# ITAC.net
KiCad netlist of a schematic drawn in Altium Designer
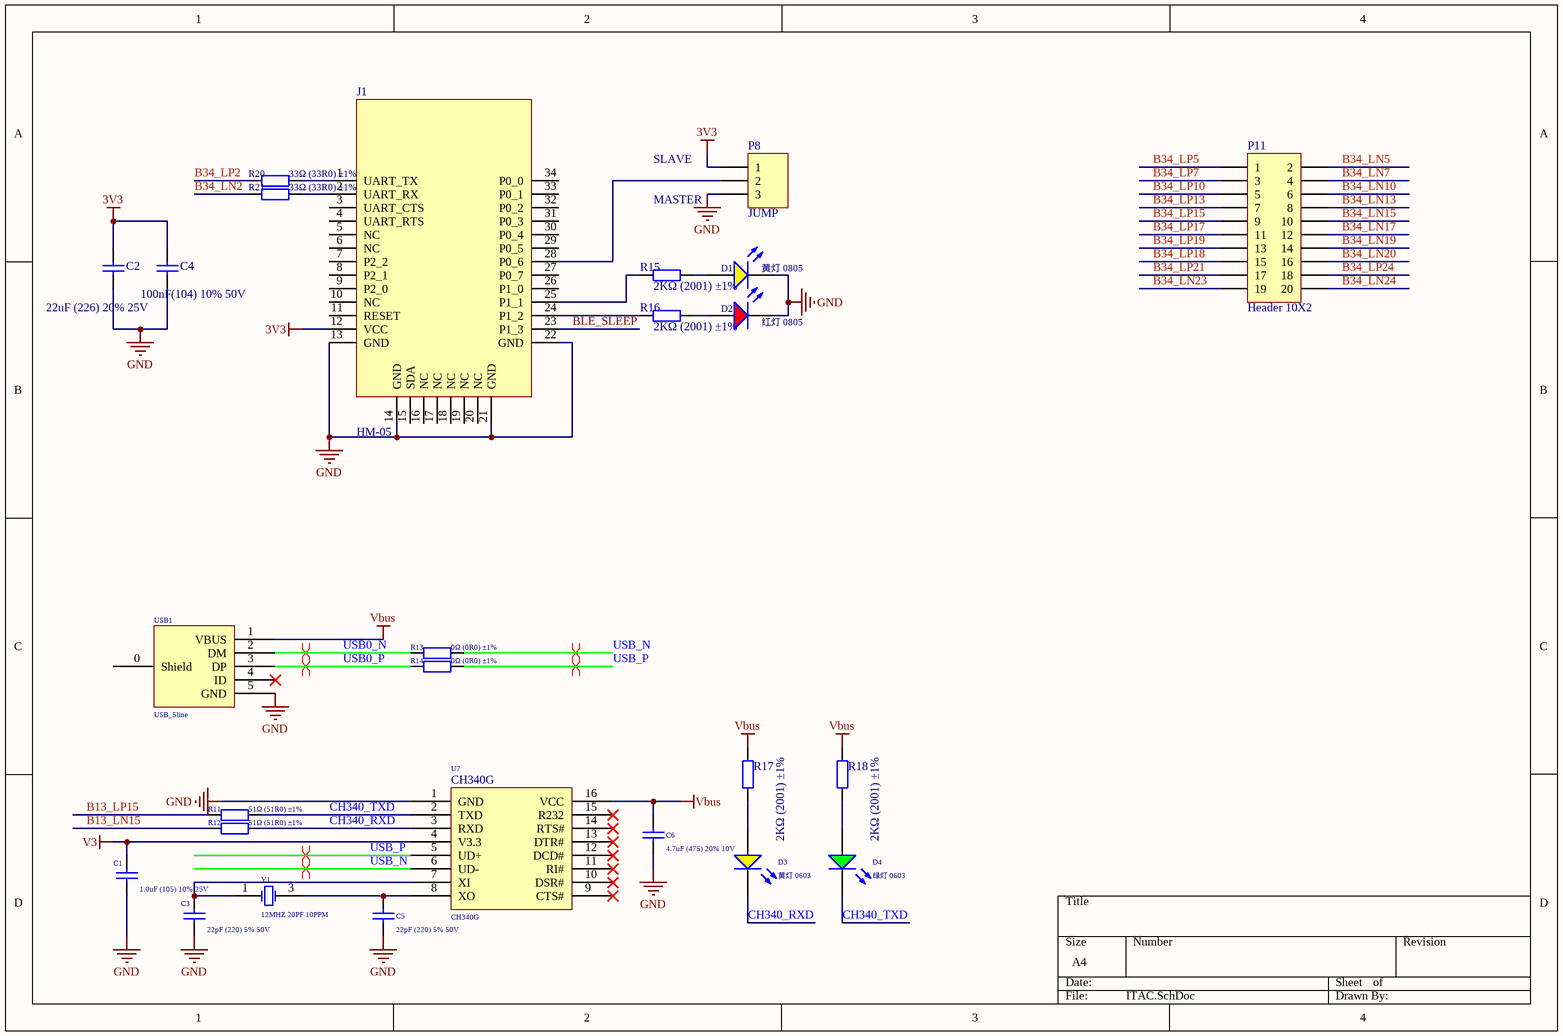
[diagram p0: ITAC.SchDoc]

(export (version "E")
  (design (tool "Eeschema 10.0.6"))
  (components
    (comp (ref "C1")
      (value "1.0uF (105) 10% 25V")
      (footprint "0402_C")
      (description "贴片电容")
      (libsource (lib "Miscellaneous Devices LC") (part "0402 1.0uF (105) 10% 25V"))
    )
    (comp (ref "C2")
      (value "22uF (226) 20% 25V")
      (footprint "0805_C")
      (description "贴片电容")
      (libsource (lib "Miscellaneous Devices LC") (part "0805 22uF (226) 20% 25V"))
    )
    (comp (ref "C3")
      (value "22pF (220) 5% 50V")
      (footprint "0402_C")
      (description "贴片电容")
      (libsource (lib "Miscellaneous Devices LC") (part "0402 22pF (220) 5% 50V"))
    )
    (comp (ref "C4")
      (value "100nF(104) 10% 50V")
      (footprint "0805_C")
      (description "贴片电容")
      (libsource (lib "Miscellaneous Devices LC") (part "0805 100nF(104) 10% 50V"))
    )
    (comp (ref "C5")
      (value "22pF (220) 5% 50V")
      (footprint "0402_C")
      (description "贴片电容")
      (libsource (lib "Miscellaneous Devices LC") (part "0402 22pF (220) 5% 50V"))
    )
    (comp (ref "C6")
      (value "4.7uF (475) 20% 10V")
      (footprint "0402_C")
      (description "贴片电容")
      (libsource (lib "Miscellaneous Devices LC") (part "0402 4.7uF (475) 20% 10V"))
    )
    (comp (ref "D1")
      (value "黄灯 0805")
      (footprint "0805_LED_S1")
      (description "发光二极管")
      (libsource (lib "Miscellaneous Devices LC") (part "0805 黄灯"))
    )
    (comp (ref "D2")
      (value "红灯 0805")
      (footprint "0805_LED_S1")
      (description "发光二极管")
      (libsource (lib "Miscellaneous Devices LC") (part "0805 红灯"))
    )
    (comp (ref "D3")
      (value "黄灯 0603")
      (footprint "0603_LED_S1")
      (description "发光二极管")
      (libsource (lib "Miscellaneous Devices LC") (part "0603 黄灯"))
    )
    (comp (ref "D4")
      (value "绿灯 0603")
      (footprint "0603_LED_S1")
      (description "发光二极管")
      (libsource (lib "Miscellaneous Devices LC") (part "0603 绿灯"))
    )
    (comp (ref "J1") (value "HM-05") (footprint "BT05") (libsource (lib "zynqEXP_Schlib") (part "HM-05")))
    (comp (ref "P8")
      (value "JUMP")
      (footprint "HDR1X3")
      (description "Header, 3-Pin")
      (fields (field (name "PUBLISHER") "Altium Limited"))
      (libsource (lib "Miscellaneous Connectors") (part "Header 3"))
    )
    (comp (ref "P11")
      (value "Header 10X2")
      (footprint "HDR2X10")
      (description "Header, 10-Pin, Dual row")
      (fields (field (name "PUBLISHER") "Altium Limited"))
      (libsource (lib "Sparks") (part "Header 10X2"))
    )
    (comp (ref "R11")
      (value "51Ω (51R0) ±1%")
      (footprint "0402_R")
      (description "贴片电阻")
      (libsource (lib "Miscellaneous Devices LC") (part "0402 51Ω (51R0) 1%"))
    )
    (comp (ref "R12")
      (value "51Ω (51R0) ±1%")
      (footprint "0402_R")
      (description "贴片电阻")
      (libsource (lib "Miscellaneous Devices LC") (part "0402 51Ω (51R0) 1%"))
    )
    (comp (ref "R13")
      (value "0Ω (0R0) ±1%")
      (footprint "0402_R")
      (description "贴片电阻")
      (libsource (lib "Miscellaneous Devices LC") (part "0402 0Ω (0R0) 1%"))
    )
    (comp (ref "R14")
      (value "0Ω (0R0) ±1%")
      (footprint "0402_R")
      (description "贴片电阻")
      (libsource (lib "Miscellaneous Devices LC") (part "0402 0Ω (0R0) 1%"))
    )
    (comp (ref "R15")
      (value "2KΩ (2001) ±1%")
      (footprint "0805_R")
      (description "贴片电阻")
      (libsource (lib "Miscellaneous Devices LC") (part "0805 2KΩ (2001) 1%"))
    )
    (comp (ref "R16")
      (value "2KΩ (2001) ±1%")
      (footprint "0805_R")
      (description "贴片电阻")
      (libsource (lib "Miscellaneous Devices LC") (part "0805 2KΩ (2001) 1%"))
    )
    (comp (ref "R17")
      (value "2KΩ (2001) ±1%")
      (footprint "0402_R")
      (description "贴片电阻")
      (libsource (lib "") (part "0402 2KΩ (2001) 1%_1"))
    )
    (comp (ref "R18")
      (value "2KΩ (2001) ±1%")
      (footprint "0402_R")
      (description "贴片电阻")
      (libsource (lib "Miscellaneous Devices LC") (part "0402 2KΩ (2001) 1%"))
    )
    (comp (ref "R20")
      (value "33Ω (33R0) ±1%")
      (footprint "0402_R")
      (description "贴片电阻")
      (libsource (lib "Miscellaneous Devices LC") (part "0402 33Ω (33R0) 1%"))
    )
    (comp (ref "R21")
      (value "33Ω (33R0) ±1%")
      (footprint "0402_R")
      (description "贴片电阻")
      (libsource (lib "Miscellaneous Devices LC") (part "0402 33Ω (33R0) 1%"))
    )
    (comp (ref "U7")
      (value "CH340G")
      (footprint "SOIC-16_150mil")
      (description "USB")
      (libsource (lib "Miscellaneous Devices LC") (part "CH340G_[C14267]"))
    )
    (comp (ref "USB1")
      (value "USB_5line")
      (footprint "USB-MICRO-5P-2F")
      (libsource (lib "2号库") (part "USB_5line"))
    )
    (comp (ref "Y1")
      (value "12MHZ 20PF 10PPM")
      (footprint "SMD-3225_4P")
      (description "贴片晶振")
      (libsource (lib "Miscellaneous Devices LC") (part "SMD-3225_4P  12MHZ 20PF 10PPM"))
    )
  )
  (nets
    (net (code "1") (name "/B13_LN15") (class "Default")
      (node (ref "R12") (pin "1") (pinfunction "1_1") (pintype "passive"))
    )
    (net (code "2") (name "/B13_LP15") (class "Default")
      (node (ref "R11") (pin "1") (pinfunction "1_1") (pintype "passive"))
    )
    (net (code "3") (name "/B34_LN2") (class "Default")
      (node (ref "R21") (pin "1") (pinfunction "1_1") (pintype "passive"))
    )
    (net (code "4") (name "/B34_LN5") (class "Default")
      (node (ref "P11") (pin "2") (pinfunction "2_2") (pintype "passive"))
    )
    (net (code "5") (name "/B34_LN7") (class "Default")
      (node (ref "P11") (pin "4") (pinfunction "4_4") (pintype "passive"))
    )
    (net (code "6") (name "/B34_LN10") (class "Default")
      (node (ref "P11") (pin "6") (pinfunction "6_6") (pintype "passive"))
    )
    (net (code "7") (name "/B34_LN13") (class "Default")
      (node (ref "P11") (pin "8") (pinfunction "8_8") (pintype "passive"))
    )
    (net (code "8") (name "/B34_LN15") (class "Default")
      (node (ref "P11") (pin "10") (pinfunction "10_10") (pintype "passive"))
    )
    (net (code "9") (name "/B34_LN17") (class "Default")
      (node (ref "P11") (pin "12") (pinfunction "12_12") (pintype "passive"))
    )
    (net (code "10") (name "/B34_LN19") (class "Default")
      (node (ref "P11") (pin "14") (pinfunction "14_14") (pintype "passive"))
    )
    (net (code "11") (name "/B34_LN20") (class "Default")
      (node (ref "P11") (pin "16") (pinfunction "16_16") (pintype "passive"))
    )
    (net (code "12") (name "/B34_LN23") (class "Default")
      (node (ref "P11") (pin "19") (pinfunction "19_19") (pintype "passive"))
    )
    (net (code "13") (name "/B34_LN24") (class "Default")
      (node (ref "P11") (pin "20") (pinfunction "20_20") (pintype "passive"))
    )
    (net (code "14") (name "/B34_LP2") (class "Default")
      (node (ref "R20") (pin "1") (pinfunction "1_1") (pintype "passive"))
    )
    (net (code "15") (name "/B34_LP5") (class "Default")
      (node (ref "P11") (pin "1") (pinfunction "1_1") (pintype "passive"))
    )
    (net (code "16") (name "/B34_LP7") (class "Default")
      (node (ref "P11") (pin "3") (pinfunction "3_3") (pintype "passive"))
    )
    (net (code "17") (name "/B34_LP10") (class "Default")
      (node (ref "P11") (pin "5") (pinfunction "5_5") (pintype "passive"))
    )
    (net (code "18") (name "/B34_LP13") (class "Default")
      (node (ref "P11") (pin "7") (pinfunction "7_7") (pintype "passive"))
    )
    (net (code "19") (name "/B34_LP15") (class "Default")
      (node (ref "P11") (pin "9") (pinfunction "9_9") (pintype "passive"))
    )
    (net (code "20") (name "/B34_LP17") (class "Default")
      (node (ref "P11") (pin "11") (pinfunction "11_11") (pintype "passive"))
    )
    (net (code "21") (name "/B34_LP18") (class "Default")
      (node (ref "P11") (pin "15") (pinfunction "15_15") (pintype "passive"))
    )
    (net (code "22") (name "/B34_LP19") (class "Default")
      (node (ref "P11") (pin "13") (pinfunction "13_13") (pintype "passive"))
    )
    (net (code "23") (name "/B34_LP21") (class "Default")
      (node (ref "P11") (pin "17") (pinfunction "17_17") (pintype "passive"))
    )
    (net (code "24") (name "/B34_LP24") (class "Default")
      (node (ref "P11") (pin "18") (pinfunction "18_18") (pintype "passive"))
    )
    (net (code "25") (name "/BLE_SLEEP") (class "Default")
      (node (ref "J1") (pin "23") (pinfunction "P1_3_23") (pintype "passive"))
    )
    (net (code "26") (name "/CH340_RXD") (class "Default")
      (node (ref "D3") (pin "K") (pinfunction "K_K") (pintype "passive"))
      (node (ref "R12") (pin "2") (pinfunction "2_2") (pintype "passive"))
      (node (ref "U7") (pin "3") (pinfunction "RXD_3") (pintype "passive"))
    )
    (net (code "27") (name "/CH340_TXD") (class "Default")
      (node (ref "D4") (pin "K") (pinfunction "K_K") (pintype "passive"))
      (node (ref "R11") (pin "2") (pinfunction "2_2") (pintype "passive"))
      (node (ref "U7") (pin "2") (pinfunction "TXD_2") (pintype "passive"))
    )
    (net (code "28") (name "/USB0_N") (class "Default")
      (node (ref "R13") (pin "1") (pinfunction "1_1") (pintype "passive"))
      (node (ref "USB1") (pin "2") (pinfunction "DM_2") (pintype "passive"))
    )
    (net (code "29") (name "/USB0_P") (class "Default")
      (node (ref "R14") (pin "1") (pinfunction "1_1") (pintype "passive"))
      (node (ref "USB1") (pin "3") (pinfunction "DP_3") (pintype "passive"))
    )
    (net (code "30") (name "/USB_N") (class "Default")
      (node (ref "R13") (pin "2") (pinfunction "2_2") (pintype "passive"))
      (node (ref "U7") (pin "6") (pinfunction "UD-_6") (pintype "passive"))
    )
    (net (code "31") (name "/USB_P") (class "Default")
      (node (ref "R14") (pin "2") (pinfunction "2_2") (pintype "passive"))
      (node (ref "U7") (pin "5") (pinfunction "UD+_5") (pintype "passive"))
    )
    (net (code "32") (name "3V3") (class "Default")
      (node (ref "C2") (pin "2") (pinfunction "2_2") (pintype "passive"))
      (node (ref "C4") (pin "2") (pinfunction "2_2") (pintype "passive"))
      (node (ref "J1") (pin "12") (pinfunction "VCC_12") (pintype "passive"))
      (node (ref "P8") (pin "1") (pinfunction "1_1") (pintype "passive"))
    )
    (net (code "33") (name "GND") (class "Default")
      (node (ref "C1") (pin "1") (pinfunction "1_1") (pintype "passive"))
      (node (ref "C2") (pin "1") (pinfunction "1_1") (pintype "passive"))
      (node (ref "C3") (pin "1") (pinfunction "1_1") (pintype "passive"))
      (node (ref "C4") (pin "1") (pinfunction "1_1") (pintype "passive"))
      (node (ref "C5") (pin "1") (pinfunction "1_1") (pintype "passive"))
      (node (ref "C6") (pin "1") (pinfunction "1_1") (pintype "passive"))
      (node (ref "D1") (pin "K") (pinfunction "K_K") (pintype "passive"))
      (node (ref "D2") (pin "K") (pinfunction "K_K") (pintype "passive"))
      (node (ref "J1") (pin "13") (pinfunction "GND_13") (pintype "passive"))
      (node (ref "J1") (pin "14") (pinfunction "GND_14") (pintype "passive"))
      (node (ref "J1") (pin "21") (pinfunction "GND_21") (pintype "passive"))
      (node (ref "J1") (pin "22") (pinfunction "GND_22") (pintype "passive"))
      (node (ref "P8") (pin "3") (pinfunction "3_3") (pintype "passive"))
      (node (ref "U7") (pin "1") (pinfunction "GND_1") (pintype "passive"))
      (node (ref "USB1") (pin "5") (pinfunction "GND_5") (pintype "passive"))
    )
    (net (code "34") (name "Net-(D1-PadA)") (class "Default")
      (node (ref "D1") (pin "A") (pinfunction "A_A") (pintype "passive"))
      (node (ref "R15") (pin "2") (pinfunction "2_2") (pintype "passive"))
    )
    (net (code "35") (name "Net-(D2-PadA)") (class "Default")
      (node (ref "D2") (pin "A") (pinfunction "A_A") (pintype "passive"))
      (node (ref "R16") (pin "2") (pinfunction "2_2") (pintype "passive"))
    )
    (net (code "36") (name "Net-(D3-PadA)") (class "Default")
      (node (ref "D3") (pin "A") (pinfunction "A_A") (pintype "passive"))
      (node (ref "R17") (pin "1") (pinfunction "1_1") (pintype "passive"))
    )
    (net (code "37") (name "Net-(D4-PadA)") (class "Default")
      (node (ref "D4") (pin "A") (pinfunction "A_A") (pintype "passive"))
      (node (ref "R18") (pin "2") (pinfunction "2_2") (pintype "passive"))
    )
    (net (code "38") (name "Net-(J1-P0_6)") (class "Default")
      (node (ref "J1") (pin "28") (pinfunction "P0_6_28") (pintype "passive"))
      (node (ref "P8") (pin "2") (pinfunction "2_2") (pintype "passive"))
    )
    (net (code "39") (name "Net-(J1-P1_1)") (class "Default")
      (node (ref "J1") (pin "25") (pinfunction "P1_1_25") (pintype "passive"))
      (node (ref "R15") (pin "1") (pinfunction "1_1") (pintype "passive"))
    )
    (net (code "40") (name "Net-(J1-P1_2)") (class "Default")
      (node (ref "J1") (pin "24") (pinfunction "P1_2_24") (pintype "passive"))
      (node (ref "R16") (pin "1") (pinfunction "1_1") (pintype "passive"))
    )
    (net (code "41") (name "Net-(J1-UART_RX)") (class "Default")
      (node (ref "J1") (pin "2") (pinfunction "UART_RX_2") (pintype "passive"))
      (node (ref "R21") (pin "2") (pinfunction "2_2") (pintype "passive"))
    )
    (net (code "42") (name "Net-(J1-UART_TX)") (class "Default")
      (node (ref "J1") (pin "1") (pinfunction "UART_TX_1") (pintype "passive"))
      (node (ref "R20") (pin "2") (pinfunction "2_2") (pintype "passive"))
    )
    (net (code "43") (name "Net-(U7-XI)") (class "Default")
      (node (ref "C3") (pin "2") (pinfunction "2_2") (pintype "passive"))
      (node (ref "U7") (pin "7") (pinfunction "XI_7") (pintype "passive"))
      (node (ref "Y1") (pin "1") (pinfunction "OSC1_1") (pintype "passive"))
    )
    (net (code "44") (name "Net-(U7-XO)") (class "Default")
      (node (ref "C5") (pin "2") (pinfunction "2_2") (pintype "passive"))
      (node (ref "U7") (pin "8") (pinfunction "XO_8") (pintype "passive"))
      (node (ref "Y1") (pin "3") (pinfunction "OSC2_3") (pintype "passive"))
    )
    (net (code "45") (name "V3") (class "Default")
      (node (ref "C1") (pin "2") (pinfunction "2_2") (pintype "passive"))
      (node (ref "U7") (pin "4") (pinfunction "V3.3_4") (pintype "passive"))
    )
    (net (code "46") (name "Vbus") (class "Default")
      (node (ref "C6") (pin "2") (pinfunction "2_2") (pintype "passive"))
      (node (ref "R17") (pin "2") (pinfunction "2_2") (pintype "passive"))
      (node (ref "R18") (pin "1") (pinfunction "1_1") (pintype "passive"))
      (node (ref "U7") (pin "16") (pinfunction "VCC_16") (pintype "passive"))
      (node (ref "USB1") (pin "1") (pinfunction "VBUS_1") (pintype "passive"))
    )
    (net (code "47") (name "unconnected-(J1-NC-Pad5)") (class "Default")
      (node (ref "J1") (pin "5") (pinfunction "NC_5") (pintype "passive"))
    )
    (net (code "48") (name "unconnected-(J1-NC-Pad6)") (class "Default")
      (node (ref "J1") (pin "6") (pinfunction "NC_6") (pintype "passive"))
    )
    (net (code "49") (name "unconnected-(J1-NC-Pad10)") (class "Default")
      (node (ref "J1") (pin "10") (pinfunction "NC_10") (pintype "passive"))
    )
    (net (code "50") (name "unconnected-(J1-NC-Pad16)") (class "Default")
      (node (ref "J1") (pin "16") (pinfunction "NC_16") (pintype "passive"))
    )
    (net (code "51") (name "unconnected-(J1-NC-Pad17)") (class "Default")
      (node (ref "J1") (pin "17") (pinfunction "NC_17") (pintype "passive"))
    )
    (net (code "52") (name "unconnected-(J1-NC-Pad18)") (class "Default")
      (node (ref "J1") (pin "18") (pinfunction "NC_18") (pintype "passive"))
    )
    (net (code "53") (name "unconnected-(J1-NC-Pad19)") (class "Default")
      (node (ref "J1") (pin "19") (pinfunction "NC_19") (pintype "passive"))
    )
    (net (code "54") (name "unconnected-(J1-NC-Pad20)") (class "Default")
      (node (ref "J1") (pin "20") (pinfunction "NC_20") (pintype "passive"))
    )
    (net (code "55") (name "unconnected-(J1-P0_0-Pad34)") (class "Default")
      (node (ref "J1") (pin "34") (pinfunction "P0_0_34") (pintype "passive"))
    )
    (net (code "56") (name "unconnected-(J1-P0_1-Pad33)") (class "Default")
      (node (ref "J1") (pin "33") (pinfunction "P0_1_33") (pintype "passive"))
    )
    (net (code "57") (name "unconnected-(J1-P0_2-Pad32)") (class "Default")
      (node (ref "J1") (pin "32") (pinfunction "P0_2_32") (pintype "passive"))
    )
    (net (code "58") (name "unconnected-(J1-P0_3-Pad31)") (class "Default")
      (node (ref "J1") (pin "31") (pinfunction "P0_3_31") (pintype "passive"))
    )
    (net (code "59") (name "unconnected-(J1-P0_4-Pad30)") (class "Default")
      (node (ref "J1") (pin "30") (pinfunction "P0_4_30") (pintype "passive"))
    )
    (net (code "60") (name "unconnected-(J1-P0_5-Pad29)") (class "Default")
      (node (ref "J1") (pin "29") (pinfunction "P0_5_29") (pintype "passive"))
    )
    (net (code "61") (name "unconnected-(J1-P0_7-Pad27)") (class "Default")
      (node (ref "J1") (pin "27") (pinfunction "P0_7_27") (pintype "passive"))
    )
    (net (code "62") (name "unconnected-(J1-P1_0-Pad26)") (class "Default")
      (node (ref "J1") (pin "26") (pinfunction "P1_0_26") (pintype "passive"))
    )
    (net (code "63") (name "unconnected-(J1-P2_0-Pad9)") (class "Default")
      (node (ref "J1") (pin "9") (pinfunction "P2_0_9") (pintype "passive"))
    )
    (net (code "64") (name "unconnected-(J1-P2_1-Pad8)") (class "Default")
      (node (ref "J1") (pin "8") (pinfunction "P2_1_8") (pintype "passive"))
    )
    (net (code "65") (name "unconnected-(J1-P2_2-Pad7)") (class "Default")
      (node (ref "J1") (pin "7") (pinfunction "P2_2_7") (pintype "passive"))
    )
    (net (code "66") (name "unconnected-(J1-RESET-Pad11)") (class "Default")
      (node (ref "J1") (pin "11") (pinfunction "RESET_11") (pintype "passive"))
    )
    (net (code "67") (name "unconnected-(J1-SDA-Pad15)") (class "Default")
      (node (ref "J1") (pin "15") (pinfunction "SDA_15") (pintype "passive"))
    )
    (net (code "68") (name "unconnected-(J1-UART_CTS-Pad3)") (class "Default")
      (node (ref "J1") (pin "3") (pinfunction "UART_CTS_3") (pintype "passive"))
    )
    (net (code "69") (name "unconnected-(J1-UART_RTS-Pad4)") (class "Default")
      (node (ref "J1") (pin "4") (pinfunction "UART_RTS_4") (pintype "passive"))
    )
    (net (code "70") (name "unconnected-(U7-CTS#-Pad9)") (class "Default")
      (node (ref "U7") (pin "9") (pinfunction "CTS#_9") (pintype "passive+no_connect"))
    )
    (net (code "71") (name "unconnected-(U7-DCD#-Pad12)") (class "Default")
      (node (ref "U7") (pin "12") (pinfunction "DCD#_12") (pintype "passive+no_connect"))
    )
    (net (code "72") (name "unconnected-(U7-DSR#-Pad10)") (class "Default")
      (node (ref "U7") (pin "10") (pinfunction "DSR#_10") (pintype "passive+no_connect"))
    )
    (net (code "73") (name "unconnected-(U7-DTR#-Pad13)") (class "Default")
      (node (ref "U7") (pin "13") (pinfunction "DTR#_13") (pintype "passive+no_connect"))
    )
    (net (code "74") (name "unconnected-(U7-R232-Pad15)") (class "Default")
      (node (ref "U7") (pin "15") (pinfunction "R232_15") (pintype "passive+no_connect"))
    )
    (net (code "75") (name "unconnected-(U7-RI#-Pad11)") (class "Default")
      (node (ref "U7") (pin "11") (pinfunction "RI#_11") (pintype "passive+no_connect"))
    )
    (net (code "76") (name "unconnected-(U7-RTS#-Pad14)") (class "Default")
      (node (ref "U7") (pin "14") (pinfunction "RTS#_14") (pintype "passive+no_connect"))
    )
    (net (code "77") (name "unconnected-(USB1-ID-Pad4)") (class "Default")
      (node (ref "USB1") (pin "4") (pinfunction "ID_4") (pintype "passive+no_connect"))
    )
    (net (code "78") (name "unconnected-(USB1-Shield-Pad0)") (class "Default")
      (node (ref "USB1") (pin "0") (pinfunction "Shield_0") (pintype "passive"))
    )
  )
)
